# AD_1.net
KiCad netlist of a schematic drawn in Altium Designer
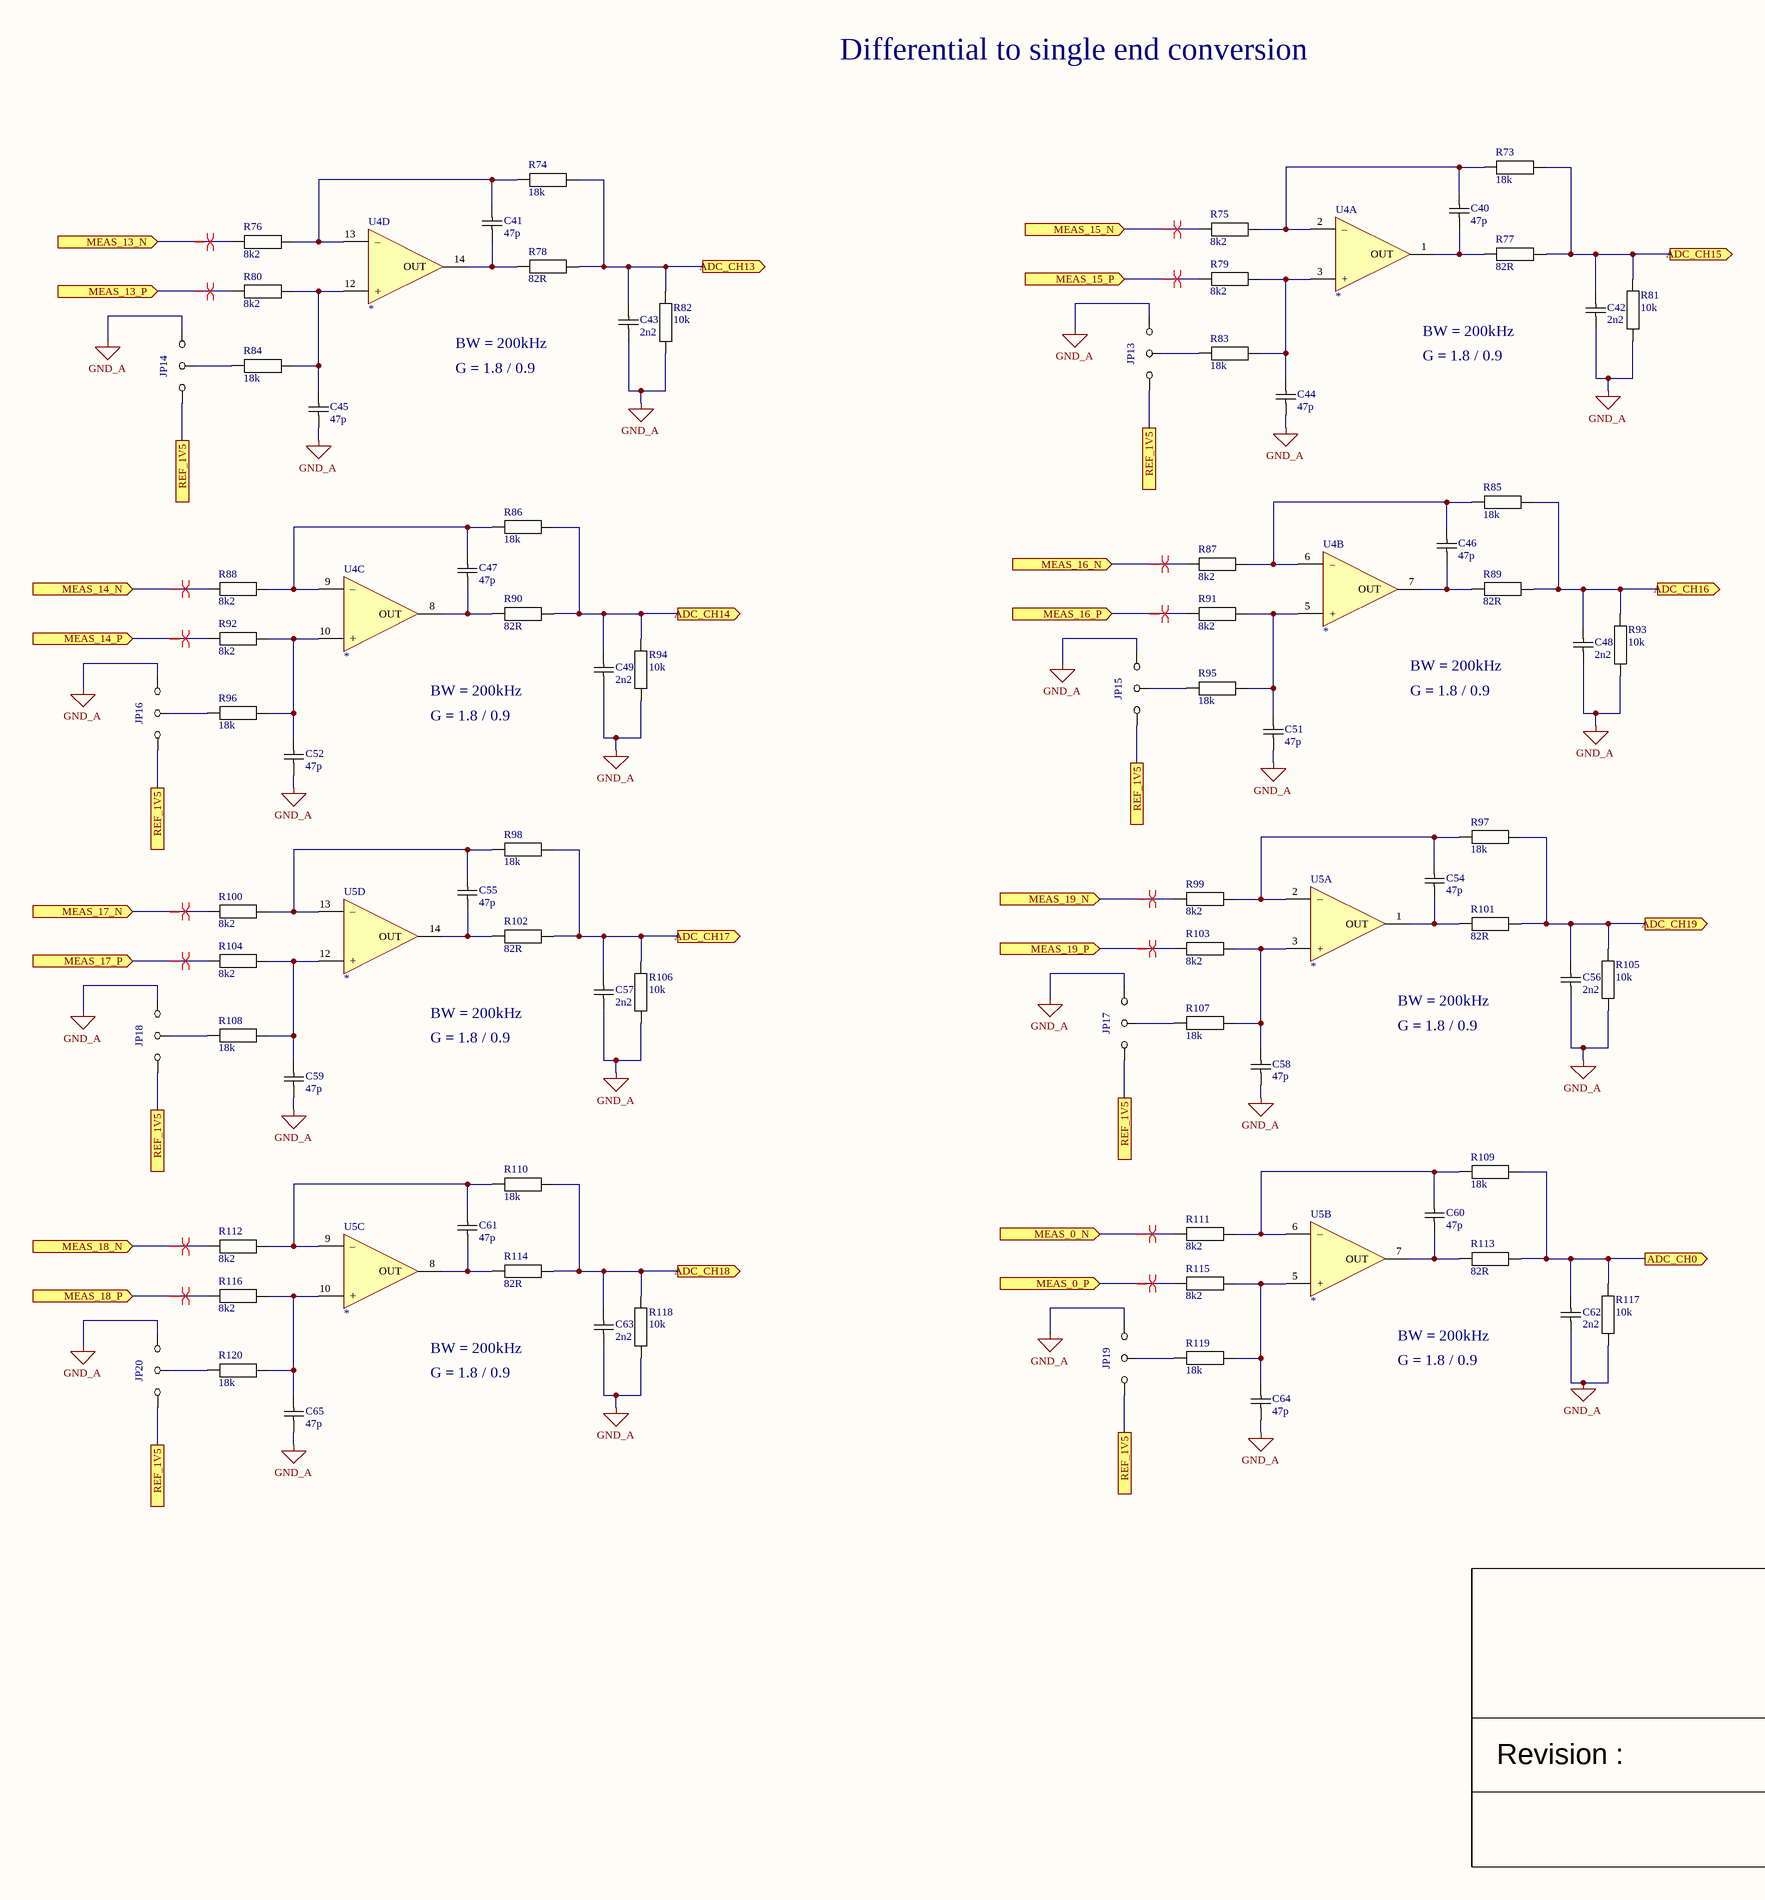
[diagram p0: AD_1.SchDoc, left]
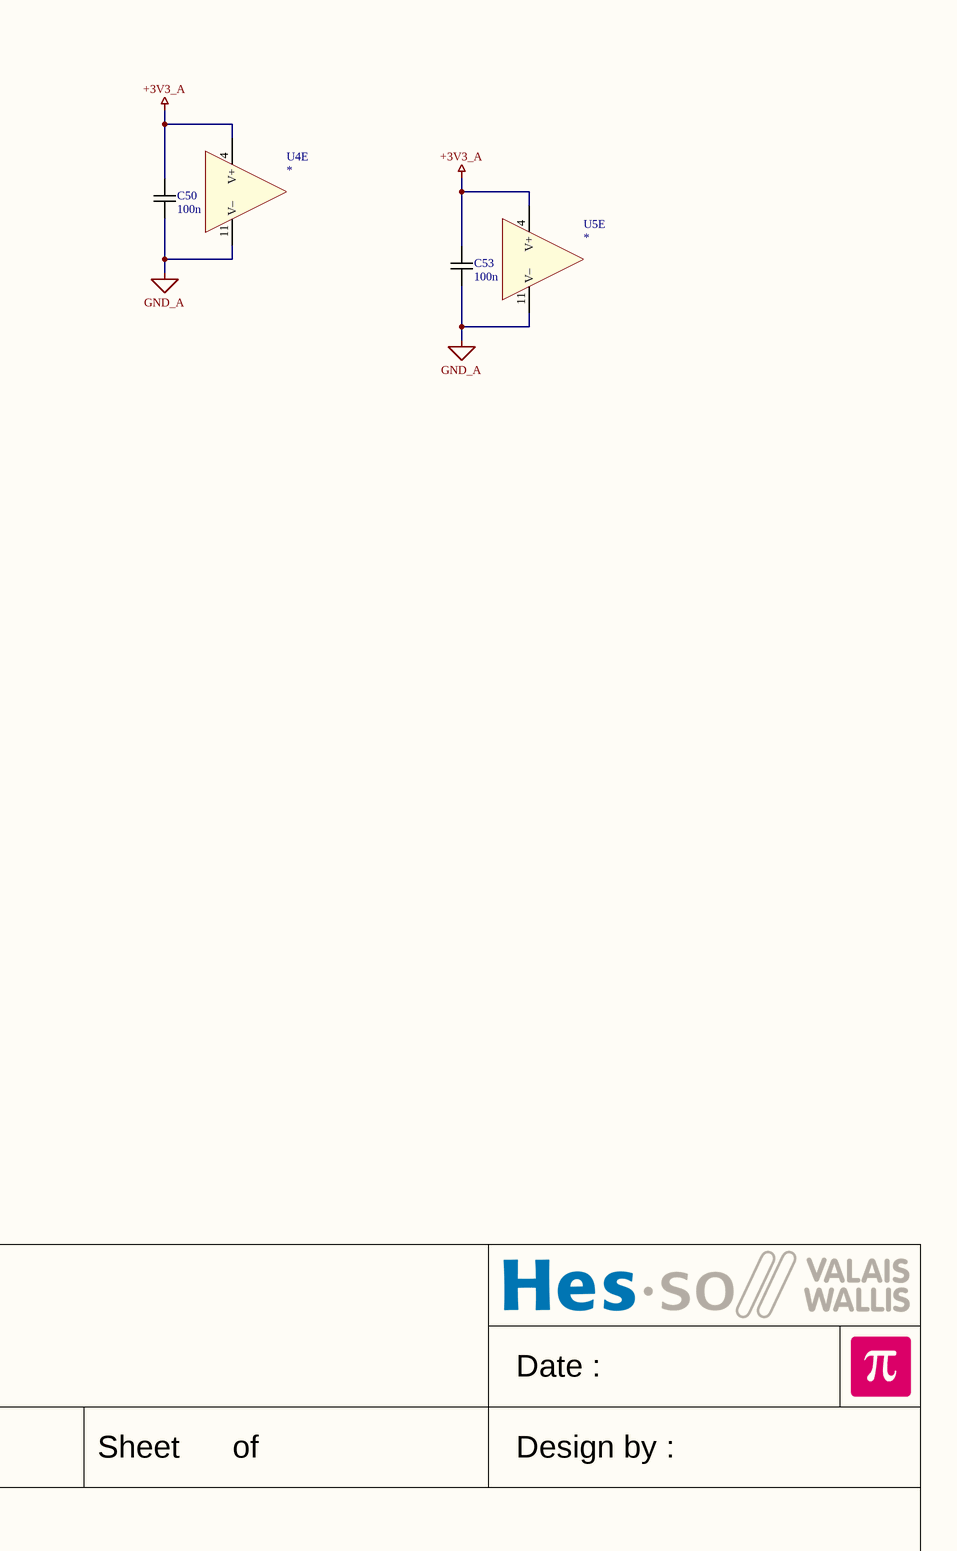
[diagram p1: AD_1.SchDoc, right]

(export (version "E")
  (design (tool "Eeschema 10.0.6"))
  (components
    (comp (ref "C40")
      (value "47p")
      (footprint "CAPACITOR 1608 REFLOW")
      (description "Capacitor X7R 10% 50V 1608(0603)")
      (libsource (lib "Capacitor") (part "Capacitor"))
    )
    (comp (ref "C41")
      (value "47p")
      (footprint "CAPACITOR 1608 REFLOW")
      (description "Capacitor X7R 10% 50V 1608(0603)")
      (libsource (lib "Capacitor") (part "Capacitor"))
    )
    (comp (ref "C42")
      (value "2n2")
      (footprint "CAPACITOR 1608 REFLOW")
      (description "Capacitor X7R 10% 50V 1608(0603)")
      (libsource (lib "Capacitor") (part "Capacitor"))
    )
    (comp (ref "C43")
      (value "2n2")
      (footprint "CAPACITOR 1608 REFLOW")
      (description "Capacitor X7R 10% 50V 1608(0603)")
      (libsource (lib "Capacitor") (part "Capacitor"))
    )
    (comp (ref "C44")
      (value "47p")
      (footprint "CAPACITOR 1608 REFLOW")
      (description "Capacitor X7R 10% 50V 1608(0603)")
      (libsource (lib "Capacitor") (part "Capacitor"))
    )
    (comp (ref "C45")
      (value "47p")
      (footprint "CAPACITOR 1608 REFLOW")
      (description "Capacitor X7R 10% 50V 1608(0603)")
      (libsource (lib "Capacitor") (part "Capacitor"))
    )
    (comp (ref "C46")
      (value "47p")
      (footprint "CAPACITOR 1608 REFLOW")
      (description "Capacitor X7R 10% 50V 1608(0603)")
      (libsource (lib "Capacitor") (part "Capacitor"))
    )
    (comp (ref "C47")
      (value "47p")
      (footprint "CAPACITOR 1608 REFLOW")
      (description "Capacitor X7R 10% 50V 1608(0603)")
      (libsource (lib "Capacitor") (part "Capacitor"))
    )
    (comp (ref "C48")
      (value "2n2")
      (footprint "CAPACITOR 1608 REFLOW")
      (description "Capacitor X7R 10% 50V 1608(0603)")
      (libsource (lib "Capacitor") (part "Capacitor"))
    )
    (comp (ref "C49")
      (value "2n2")
      (footprint "CAPACITOR 1608 REFLOW")
      (description "Capacitor X7R 10% 50V 1608(0603)")
      (libsource (lib "Capacitor") (part "Capacitor"))
    )
    (comp (ref "C50")
      (value "100n")
      (footprint "CAPACITOR 1608 REFLOW")
      (description "Capacitor X7R 10% 50V 1608(0603)")
      (libsource (lib "Capacitor") (part "Capacitor"))
    )
    (comp (ref "C51")
      (value "47p")
      (footprint "CAPACITOR 1608 REFLOW")
      (description "Capacitor X7R 10% 50V 1608(0603)")
      (libsource (lib "Capacitor") (part "Capacitor"))
    )
    (comp (ref "C52")
      (value "47p")
      (footprint "CAPACITOR 1608 REFLOW")
      (description "Capacitor X7R 10% 50V 1608(0603)")
      (libsource (lib "Capacitor") (part "Capacitor"))
    )
    (comp (ref "C53")
      (value "100n")
      (footprint "CAPACITOR 1608 REFLOW")
      (description "Capacitor X7R 10% 50V 1608(0603)")
      (libsource (lib "Capacitor") (part "Capacitor"))
    )
    (comp (ref "C54")
      (value "47p")
      (footprint "CAPACITOR 1608 REFLOW")
      (description "Capacitor X7R 10% 50V 1608(0603)")
      (libsource (lib "Capacitor") (part "Capacitor"))
    )
    (comp (ref "C55")
      (value "47p")
      (footprint "CAPACITOR 1608 REFLOW")
      (description "Capacitor X7R 10% 50V 1608(0603)")
      (libsource (lib "Capacitor") (part "Capacitor"))
    )
    (comp (ref "C56")
      (value "2n2")
      (footprint "CAPACITOR 1608 REFLOW")
      (description "Capacitor X7R 10% 50V 1608(0603)")
      (libsource (lib "Capacitor") (part "Capacitor"))
    )
    (comp (ref "C57")
      (value "2n2")
      (footprint "CAPACITOR 1608 REFLOW")
      (description "Capacitor X7R 10% 50V 1608(0603)")
      (libsource (lib "Capacitor") (part "Capacitor"))
    )
    (comp (ref "C58")
      (value "47p")
      (footprint "CAPACITOR 1608 REFLOW")
      (description "Capacitor X7R 10% 50V 1608(0603)")
      (libsource (lib "Capacitor") (part "Capacitor"))
    )
    (comp (ref "C59")
      (value "47p")
      (footprint "CAPACITOR 1608 REFLOW")
      (description "Capacitor X7R 10% 50V 1608(0603)")
      (libsource (lib "Capacitor") (part "Capacitor"))
    )
    (comp (ref "C60")
      (value "47p")
      (footprint "CAPACITOR 1608 REFLOW")
      (description "Capacitor X7R 10% 50V 1608(0603)")
      (libsource (lib "Capacitor") (part "Capacitor"))
    )
    (comp (ref "C61")
      (value "47p")
      (footprint "CAPACITOR 1608 REFLOW")
      (description "Capacitor X7R 10% 50V 1608(0603)")
      (libsource (lib "Capacitor") (part "Capacitor"))
    )
    (comp (ref "C62")
      (value "2n2")
      (footprint "CAPACITOR 1608 REFLOW")
      (description "Capacitor X7R 10% 50V 1608(0603)")
      (libsource (lib "Capacitor") (part "Capacitor"))
    )
    (comp (ref "C63")
      (value "2n2")
      (footprint "CAPACITOR 1608 REFLOW")
      (description "Capacitor X7R 10% 50V 1608(0603)")
      (libsource (lib "Capacitor") (part "Capacitor"))
    )
    (comp (ref "C64")
      (value "47p")
      (footprint "CAPACITOR 1608 REFLOW")
      (description "Capacitor X7R 10% 50V 1608(0603)")
      (libsource (lib "Capacitor") (part "Capacitor"))
    )
    (comp (ref "C65")
      (value "47p")
      (footprint "CAPACITOR 1608 REFLOW")
      (description "Capacitor X7R 10% 50V 1608(0603)")
      (libsource (lib "Capacitor") (part "Capacitor"))
    )
    (comp (ref "JP13")
      (value "{Value}")
      (footprint "JUMPER3 SMD 1608")
      (description "JUMPER 3 POS")
      (libsource (lib "Jumper") (part "JUMPER 3 POS"))
    )
    (comp (ref "JP14")
      (value "{Value}")
      (footprint "JUMPER3 SMD 1608")
      (description "JUMPER 3 POS")
      (libsource (lib "Jumper") (part "JUMPER 3 POS"))
    )
    (comp (ref "JP15")
      (value "{Value}")
      (footprint "JUMPER3 SMD 1608")
      (description "JUMPER 3 POS")
      (libsource (lib "Jumper") (part "JUMPER 3 POS"))
    )
    (comp (ref "JP16")
      (value "{Value}")
      (footprint "JUMPER3 SMD 1608")
      (description "JUMPER 3 POS")
      (libsource (lib "Jumper") (part "JUMPER 3 POS"))
    )
    (comp (ref "JP17")
      (value "{Value}")
      (footprint "JUMPER3 SMD 1608")
      (description "JUMPER 3 POS")
      (libsource (lib "Jumper") (part "JUMPER 3 POS"))
    )
    (comp (ref "JP18")
      (value "{Value}")
      (footprint "JUMPER3 SMD 1608")
      (description "JUMPER 3 POS")
      (libsource (lib "Jumper") (part "JUMPER 3 POS"))
    )
    (comp (ref "JP19")
      (value "{Value}")
      (footprint "JUMPER3 SMD 1608")
      (description "JUMPER 3 POS")
      (libsource (lib "Jumper") (part "JUMPER 3 POS"))
    )
    (comp (ref "JP20")
      (value "{Value}")
      (footprint "JUMPER3 SMD 1608")
      (description "JUMPER 3 POS")
      (libsource (lib "Jumper") (part "JUMPER 3 POS"))
    )
    (comp (ref "R73")
      (value "18k")
      (footprint "RESISTOR 1608 REFLOW")
      (description "Resistor 1% 50V 100mW 1608(0603)")
      (libsource (lib "Resistor") (part "Resistor"))
    )
    (comp (ref "R74")
      (value "18k")
      (footprint "RESISTOR 1608 REFLOW")
      (description "Resistor 1% 50V 100mW 1608(0603)")
      (libsource (lib "Resistor") (part "Resistor"))
    )
    (comp (ref "R75")
      (value "8k2")
      (footprint "RESISTOR 1608 REFLOW")
      (description "Resistor 1% 50V 100mW 1608(0603)")
      (libsource (lib "Resistor") (part "Resistor"))
    )
    (comp (ref "R76")
      (value "8k2")
      (footprint "RESISTOR 1608 REFLOW")
      (description "Resistor 1% 50V 100mW 1608(0603)")
      (libsource (lib "Resistor") (part "Resistor"))
    )
    (comp (ref "R77")
      (value "82R")
      (footprint "RESISTOR 1608 REFLOW")
      (description "Resistor 1% 50V 100mW 1608(0603)")
      (libsource (lib "Resistor") (part "Resistor"))
    )
    (comp (ref "R78")
      (value "82R")
      (footprint "RESISTOR 1608 REFLOW")
      (description "Resistor 1% 50V 100mW 1608(0603)")
      (libsource (lib "Resistor") (part "Resistor"))
    )
    (comp (ref "R79")
      (value "8k2")
      (footprint "RESISTOR 1608 REFLOW")
      (description "Resistor 1% 50V 100mW 1608(0603)")
      (libsource (lib "Resistor") (part "Resistor"))
    )
    (comp (ref "R80")
      (value "8k2")
      (footprint "RESISTOR 1608 REFLOW")
      (description "Resistor 1% 50V 100mW 1608(0603)")
      (libsource (lib "Resistor") (part "Resistor"))
    )
    (comp (ref "R81")
      (value "10k")
      (footprint "RESISTOR 1608 REFLOW")
      (description "Resistor 1% 50V 100mW 1608(0603)")
      (libsource (lib "Resistor") (part "Resistor"))
    )
    (comp (ref "R82")
      (value "10k")
      (footprint "RESISTOR 1608 REFLOW")
      (description "Resistor 1% 50V 100mW 1608(0603)")
      (libsource (lib "Resistor") (part "Resistor"))
    )
    (comp (ref "R83")
      (value "18k")
      (footprint "RESISTOR 1608 REFLOW")
      (description "Resistor 1% 50V 100mW 1608(0603)")
      (libsource (lib "Resistor") (part "Resistor"))
    )
    (comp (ref "R84")
      (value "18k")
      (footprint "RESISTOR 1608 REFLOW")
      (description "Resistor 1% 50V 100mW 1608(0603)")
      (libsource (lib "Resistor") (part "Resistor"))
    )
    (comp (ref "R85")
      (value "18k")
      (footprint "RESISTOR 1608 REFLOW")
      (description "Resistor 1% 50V 100mW 1608(0603)")
      (libsource (lib "Resistor") (part "Resistor"))
    )
    (comp (ref "R86")
      (value "18k")
      (footprint "RESISTOR 1608 REFLOW")
      (description "Resistor 1% 50V 100mW 1608(0603)")
      (libsource (lib "Resistor") (part "Resistor"))
    )
    (comp (ref "R87")
      (value "8k2")
      (footprint "RESISTOR 1608 REFLOW")
      (description "Resistor 1% 50V 100mW 1608(0603)")
      (libsource (lib "Resistor") (part "Resistor"))
    )
    (comp (ref "R88")
      (value "8k2")
      (footprint "RESISTOR 1608 REFLOW")
      (description "Resistor 1% 50V 100mW 1608(0603)")
      (libsource (lib "Resistor") (part "Resistor"))
    )
    (comp (ref "R89")
      (value "82R")
      (footprint "RESISTOR 1608 REFLOW")
      (description "Resistor 1% 50V 100mW 1608(0603)")
      (libsource (lib "Resistor") (part "Resistor"))
    )
    (comp (ref "R90")
      (value "82R")
      (footprint "RESISTOR 1608 REFLOW")
      (description "Resistor 1% 50V 100mW 1608(0603)")
      (libsource (lib "Resistor") (part "Resistor"))
    )
    (comp (ref "R91")
      (value "8k2")
      (footprint "RESISTOR 1608 REFLOW")
      (description "Resistor 1% 50V 100mW 1608(0603)")
      (libsource (lib "Resistor") (part "Resistor"))
    )
    (comp (ref "R92")
      (value "8k2")
      (footprint "RESISTOR 1608 REFLOW")
      (description "Resistor 1% 50V 100mW 1608(0603)")
      (libsource (lib "Resistor") (part "Resistor"))
    )
    (comp (ref "R93")
      (value "10k")
      (footprint "RESISTOR 1608 REFLOW")
      (description "Resistor 1% 50V 100mW 1608(0603)")
      (libsource (lib "Resistor") (part "Resistor"))
    )
    (comp (ref "R94")
      (value "10k")
      (footprint "RESISTOR 1608 REFLOW")
      (description "Resistor 1% 50V 100mW 1608(0603)")
      (libsource (lib "Resistor") (part "Resistor"))
    )
    (comp (ref "R95")
      (value "18k")
      (footprint "RESISTOR 1608 REFLOW")
      (description "Resistor 1% 50V 100mW 1608(0603)")
      (libsource (lib "Resistor") (part "Resistor"))
    )
    (comp (ref "R96")
      (value "18k")
      (footprint "RESISTOR 1608 REFLOW")
      (description "Resistor 1% 50V 100mW 1608(0603)")
      (libsource (lib "Resistor") (part "Resistor"))
    )
    (comp (ref "R97")
      (value "18k")
      (footprint "RESISTOR 1608 REFLOW")
      (description "Resistor 1% 50V 100mW 1608(0603)")
      (libsource (lib "Resistor") (part "Resistor"))
    )
    (comp (ref "R98")
      (value "18k")
      (footprint "RESISTOR 1608 REFLOW")
      (description "Resistor 1% 50V 100mW 1608(0603)")
      (libsource (lib "Resistor") (part "Resistor"))
    )
    (comp (ref "R99")
      (value "8k2")
      (footprint "RESISTOR 1608 REFLOW")
      (description "Resistor 1% 50V 100mW 1608(0603)")
      (libsource (lib "Resistor") (part "Resistor"))
    )
    (comp (ref "R100")
      (value "8k2")
      (footprint "RESISTOR 1608 REFLOW")
      (description "Resistor 1% 50V 100mW 1608(0603)")
      (libsource (lib "Resistor") (part "Resistor"))
    )
    (comp (ref "R101")
      (value "82R")
      (footprint "RESISTOR 1608 REFLOW")
      (description "Resistor 1% 50V 100mW 1608(0603)")
      (libsource (lib "Resistor") (part "Resistor"))
    )
    (comp (ref "R102")
      (value "82R")
      (footprint "RESISTOR 1608 REFLOW")
      (description "Resistor 1% 50V 100mW 1608(0603)")
      (libsource (lib "Resistor") (part "Resistor"))
    )
    (comp (ref "R103")
      (value "8k2")
      (footprint "RESISTOR 1608 REFLOW")
      (description "Resistor 1% 50V 100mW 1608(0603)")
      (libsource (lib "Resistor") (part "Resistor"))
    )
    (comp (ref "R104")
      (value "8k2")
      (footprint "RESISTOR 1608 REFLOW")
      (description "Resistor 1% 50V 100mW 1608(0603)")
      (libsource (lib "Resistor") (part "Resistor"))
    )
    (comp (ref "R105")
      (value "10k")
      (footprint "RESISTOR 1608 REFLOW")
      (description "Resistor 1% 50V 100mW 1608(0603)")
      (libsource (lib "Resistor") (part "Resistor"))
    )
    (comp (ref "R106")
      (value "10k")
      (footprint "RESISTOR 1608 REFLOW")
      (description "Resistor 1% 50V 100mW 1608(0603)")
      (libsource (lib "Resistor") (part "Resistor"))
    )
    (comp (ref "R107")
      (value "18k")
      (footprint "RESISTOR 1608 REFLOW")
      (description "Resistor 1% 50V 100mW 1608(0603)")
      (libsource (lib "Resistor") (part "Resistor"))
    )
    (comp (ref "R108")
      (value "18k")
      (footprint "RESISTOR 1608 REFLOW")
      (description "Resistor 1% 50V 100mW 1608(0603)")
      (libsource (lib "Resistor") (part "Resistor"))
    )
    (comp (ref "R109")
      (value "18k")
      (footprint "RESISTOR 1608 REFLOW")
      (description "Resistor 1% 50V 100mW 1608(0603)")
      (libsource (lib "Resistor") (part "Resistor"))
    )
    (comp (ref "R110")
      (value "18k")
      (footprint "RESISTOR 1608 REFLOW")
      (description "Resistor 1% 50V 100mW 1608(0603)")
      (libsource (lib "Resistor") (part "Resistor"))
    )
    (comp (ref "R111")
      (value "8k2")
      (footprint "RESISTOR 1608 REFLOW")
      (description "Resistor 1% 50V 100mW 1608(0603)")
      (libsource (lib "Resistor") (part "Resistor"))
    )
    (comp (ref "R112")
      (value "8k2")
      (footprint "RESISTOR 1608 REFLOW")
      (description "Resistor 1% 50V 100mW 1608(0603)")
      (libsource (lib "Resistor") (part "Resistor"))
    )
    (comp (ref "R113")
      (value "82R")
      (footprint "RESISTOR 1608 REFLOW")
      (description "Resistor 1% 50V 100mW 1608(0603)")
      (libsource (lib "Resistor") (part "Resistor"))
    )
    (comp (ref "R114")
      (value "82R")
      (footprint "RESISTOR 1608 REFLOW")
      (description "Resistor 1% 50V 100mW 1608(0603)")
      (libsource (lib "Resistor") (part "Resistor"))
    )
    (comp (ref "R115")
      (value "8k2")
      (footprint "RESISTOR 1608 REFLOW")
      (description "Resistor 1% 50V 100mW 1608(0603)")
      (libsource (lib "Resistor") (part "Resistor"))
    )
    (comp (ref "R116")
      (value "8k2")
      (footprint "RESISTOR 1608 REFLOW")
      (description "Resistor 1% 50V 100mW 1608(0603)")
      (libsource (lib "Resistor") (part "Resistor"))
    )
    (comp (ref "R117")
      (value "10k")
      (footprint "RESISTOR 1608 REFLOW")
      (description "Resistor 1% 50V 100mW 1608(0603)")
      (libsource (lib "Resistor") (part "Resistor"))
    )
    (comp (ref "R118")
      (value "10k")
      (footprint "RESISTOR 1608 REFLOW")
      (description "Resistor 1% 50V 100mW 1608(0603)")
      (libsource (lib "Resistor") (part "Resistor"))
    )
    (comp (ref "R119")
      (value "18k")
      (footprint "RESISTOR 1608 REFLOW")
      (description "Resistor 1% 50V 100mW 1608(0603)")
      (libsource (lib "Resistor") (part "Resistor"))
    )
    (comp (ref "R120")
      (value "18k")
      (footprint "RESISTOR 1608 REFLOW")
      (description "Resistor 1% 50V 100mW 1608(0603)")
      (libsource (lib "Resistor") (part "Resistor"))
    )
    (comp (ref "U4")
      (value "*")
      (footprint "SO14 P1.27 C4.0X8.8 H1.75")
      (description "Generic quad OPA 14 pins")
      (libsource (lib "Amplifier") (part "OPA QUAD"))
    )
    (comp (ref "U5")
      (value "*")
      (footprint "SO14 P1.27 C4.0X8.8 H1.75")
      (description "Generic quad OPA 14 pins")
      (libsource (lib "Amplifier") (part "OPA QUAD"))
    )
  )
  (nets
    (net (code "1") (name "+3V3_A") (class "Default")
      (node (ref "C50") (pin "2") (pinfunction "2_2") (pintype "passive"))
      (node (ref "C53") (pin "2") (pinfunction "2_2") (pintype "passive"))
      (node (ref "U4") (pin "4") (pinfunction "V+_4") (pintype "passive"))
      (node (ref "U5") (pin "4") (pinfunction "V+_4") (pintype "passive"))
    )
    (net (code "2") (name "/ADC_CH0") (class "Default")
      (node (ref "C62") (pin "2") (pinfunction "2_2") (pintype "passive"))
      (node (ref "R109") (pin "2") (pinfunction "2_2") (pintype "passive"))
      (node (ref "R113") (pin "2") (pinfunction "2_2") (pintype "passive"))
      (node (ref "R117") (pin "1") (pinfunction "1_1") (pintype "passive"))
    )
    (net (code "3") (name "/ADC_CH13") (class "Default")
      (node (ref "C43") (pin "2") (pinfunction "2_2") (pintype "passive"))
      (node (ref "R74") (pin "2") (pinfunction "2_2") (pintype "passive"))
      (node (ref "R78") (pin "2") (pinfunction "2_2") (pintype "passive"))
      (node (ref "R82") (pin "1") (pinfunction "1_1") (pintype "passive"))
    )
    (net (code "4") (name "/ADC_CH14") (class "Default")
      (node (ref "C49") (pin "2") (pinfunction "2_2") (pintype "passive"))
      (node (ref "R86") (pin "2") (pinfunction "2_2") (pintype "passive"))
      (node (ref "R90") (pin "2") (pinfunction "2_2") (pintype "passive"))
      (node (ref "R94") (pin "1") (pinfunction "1_1") (pintype "passive"))
    )
    (net (code "5") (name "/ADC_CH15") (class "Default")
      (node (ref "C42") (pin "2") (pinfunction "2_2") (pintype "passive"))
      (node (ref "R73") (pin "2") (pinfunction "2_2") (pintype "passive"))
      (node (ref "R77") (pin "2") (pinfunction "2_2") (pintype "passive"))
      (node (ref "R81") (pin "1") (pinfunction "1_1") (pintype "passive"))
    )
    (net (code "6") (name "/ADC_CH16") (class "Default")
      (node (ref "C48") (pin "2") (pinfunction "2_2") (pintype "passive"))
      (node (ref "R85") (pin "2") (pinfunction "2_2") (pintype "passive"))
      (node (ref "R89") (pin "2") (pinfunction "2_2") (pintype "passive"))
      (node (ref "R93") (pin "1") (pinfunction "1_1") (pintype "passive"))
    )
    (net (code "7") (name "/ADC_CH17") (class "Default")
      (node (ref "C57") (pin "2") (pinfunction "2_2") (pintype "passive"))
      (node (ref "R102") (pin "2") (pinfunction "2_2") (pintype "passive"))
      (node (ref "R106") (pin "1") (pinfunction "1_1") (pintype "passive"))
      (node (ref "R98") (pin "2") (pinfunction "2_2") (pintype "passive"))
    )
    (net (code "8") (name "/ADC_CH18") (class "Default")
      (node (ref "C63") (pin "2") (pinfunction "2_2") (pintype "passive"))
      (node (ref "R110") (pin "2") (pinfunction "2_2") (pintype "passive"))
      (node (ref "R114") (pin "2") (pinfunction "2_2") (pintype "passive"))
      (node (ref "R118") (pin "1") (pinfunction "1_1") (pintype "passive"))
    )
    (net (code "9") (name "/ADC_CH19") (class "Default")
      (node (ref "C56") (pin "2") (pinfunction "2_2") (pintype "passive"))
      (node (ref "R101") (pin "2") (pinfunction "2_2") (pintype "passive"))
      (node (ref "R105") (pin "1") (pinfunction "1_1") (pintype "passive"))
      (node (ref "R97") (pin "2") (pinfunction "2_2") (pintype "passive"))
    )
    (net (code "10") (name "/MEAS_0_N") (class "Default")
      (node (ref "R111") (pin "1") (pinfunction "1_1") (pintype "passive"))
    )
    (net (code "11") (name "/MEAS_0_P") (class "Default")
      (node (ref "R115") (pin "1") (pinfunction "1_1") (pintype "passive"))
    )
    (net (code "12") (name "/MEAS_13_N") (class "Default")
      (node (ref "R76") (pin "1") (pinfunction "1_1") (pintype "passive"))
    )
    (net (code "13") (name "/MEAS_13_P") (class "Default")
      (node (ref "R80") (pin "1") (pinfunction "1_1") (pintype "passive"))
    )
    (net (code "14") (name "/MEAS_14_N") (class "Default")
      (node (ref "R88") (pin "1") (pinfunction "1_1") (pintype "passive"))
    )
    (net (code "15") (name "/MEAS_14_P") (class "Default")
      (node (ref "R92") (pin "1") (pinfunction "1_1") (pintype "passive"))
    )
    (net (code "16") (name "/MEAS_15_N") (class "Default")
      (node (ref "R75") (pin "1") (pinfunction "1_1") (pintype "passive"))
    )
    (net (code "17") (name "/MEAS_15_P") (class "Default")
      (node (ref "R79") (pin "1") (pinfunction "1_1") (pintype "passive"))
    )
    (net (code "18") (name "/MEAS_16_N") (class "Default")
      (node (ref "R87") (pin "1") (pinfunction "1_1") (pintype "passive"))
    )
    (net (code "19") (name "/MEAS_16_P") (class "Default")
      (node (ref "R91") (pin "1") (pinfunction "1_1") (pintype "passive"))
    )
    (net (code "20") (name "/MEAS_17_N") (class "Default")
      (node (ref "R100") (pin "1") (pinfunction "1_1") (pintype "passive"))
    )
    (net (code "21") (name "/MEAS_17_P") (class "Default")
      (node (ref "R104") (pin "1") (pinfunction "1_1") (pintype "passive"))
    )
    (net (code "22") (name "/MEAS_18_N") (class "Default")
      (node (ref "R112") (pin "1") (pinfunction "1_1") (pintype "passive"))
    )
    (net (code "23") (name "/MEAS_18_P") (class "Default")
      (node (ref "R116") (pin "1") (pinfunction "1_1") (pintype "passive"))
    )
    (net (code "24") (name "/MEAS_19_N") (class "Default")
      (node (ref "R99") (pin "1") (pinfunction "1_1") (pintype "passive"))
    )
    (net (code "25") (name "/MEAS_19_P") (class "Default")
      (node (ref "R103") (pin "1") (pinfunction "1_1") (pintype "passive"))
    )
    (net (code "26") (name "/REF_1V5") (class "Default")
      (node (ref "JP13") (pin "1") (pinfunction "1_1") (pintype "passive"))
      (node (ref "JP14") (pin "1") (pinfunction "1_1") (pintype "passive"))
      (node (ref "JP15") (pin "1") (pinfunction "1_1") (pintype "passive"))
      (node (ref "JP16") (pin "1") (pinfunction "1_1") (pintype "passive"))
      (node (ref "JP17") (pin "1") (pinfunction "1_1") (pintype "passive"))
      (node (ref "JP18") (pin "1") (pinfunction "1_1") (pintype "passive"))
      (node (ref "JP19") (pin "1") (pinfunction "1_1") (pintype "passive"))
      (node (ref "JP20") (pin "1") (pinfunction "1_1") (pintype "passive"))
    )
    (net (code "27") (name "GND_A") (class "Default")
      (node (ref "C42") (pin "1") (pinfunction "1_1") (pintype "passive"))
      (node (ref "C43") (pin "1") (pinfunction "1_1") (pintype "passive"))
      (node (ref "C44") (pin "1") (pinfunction "1_1") (pintype "passive"))
      (node (ref "C45") (pin "1") (pinfunction "1_1") (pintype "passive"))
      (node (ref "C48") (pin "1") (pinfunction "1_1") (pintype "passive"))
      (node (ref "C49") (pin "1") (pinfunction "1_1") (pintype "passive"))
      (node (ref "C50") (pin "1") (pinfunction "1_1") (pintype "passive"))
      (node (ref "C51") (pin "1") (pinfunction "1_1") (pintype "passive"))
      (node (ref "C52") (pin "1") (pinfunction "1_1") (pintype "passive"))
      (node (ref "C53") (pin "1") (pinfunction "1_1") (pintype "passive"))
      (node (ref "C56") (pin "1") (pinfunction "1_1") (pintype "passive"))
      (node (ref "C57") (pin "1") (pinfunction "1_1") (pintype "passive"))
      (node (ref "C58") (pin "1") (pinfunction "1_1") (pintype "passive"))
      (node (ref "C59") (pin "1") (pinfunction "1_1") (pintype "passive"))
      (node (ref "C62") (pin "1") (pinfunction "1_1") (pintype "passive"))
      (node (ref "C63") (pin "1") (pinfunction "1_1") (pintype "passive"))
      (node (ref "C64") (pin "1") (pinfunction "1_1") (pintype "passive"))
      (node (ref "C65") (pin "1") (pinfunction "1_1") (pintype "passive"))
      (node (ref "JP13") (pin "3") (pinfunction "3_3") (pintype "passive"))
      (node (ref "JP14") (pin "3") (pinfunction "3_3") (pintype "passive"))
      (node (ref "JP15") (pin "3") (pinfunction "3_3") (pintype "passive"))
      (node (ref "JP16") (pin "3") (pinfunction "3_3") (pintype "passive"))
      (node (ref "JP17") (pin "3") (pinfunction "3_3") (pintype "passive"))
      (node (ref "JP18") (pin "3") (pinfunction "3_3") (pintype "passive"))
      (node (ref "JP19") (pin "3") (pinfunction "3_3") (pintype "passive"))
      (node (ref "JP20") (pin "3") (pinfunction "3_3") (pintype "passive"))
      (node (ref "R105") (pin "2") (pinfunction "2_2") (pintype "passive"))
      (node (ref "R106") (pin "2") (pinfunction "2_2") (pintype "passive"))
      (node (ref "R117") (pin "2") (pinfunction "2_2") (pintype "passive"))
      (node (ref "R118") (pin "2") (pinfunction "2_2") (pintype "passive"))
      (node (ref "R81") (pin "2") (pinfunction "2_2") (pintype "passive"))
      (node (ref "R82") (pin "2") (pinfunction "2_2") (pintype "passive"))
      (node (ref "R93") (pin "2") (pinfunction "2_2") (pintype "passive"))
      (node (ref "R94") (pin "2") (pinfunction "2_2") (pintype "passive"))
      (node (ref "U4") (pin "11") (pinfunction "V–_11") (pintype "passive"))
      (node (ref "U5") (pin "11") (pinfunction "V–_11") (pintype "passive"))
    )
    (net (code "28") (name "Net-(JP13-Pad2)") (class "Default")
      (node (ref "JP13") (pin "2") (pinfunction "2_2") (pintype "passive"))
      (node (ref "R83") (pin "2") (pinfunction "2_2") (pintype "passive"))
    )
    (net (code "29") (name "Net-(JP14-Pad2)") (class "Default")
      (node (ref "JP14") (pin "2") (pinfunction "2_2") (pintype "passive"))
      (node (ref "R84") (pin "2") (pinfunction "2_2") (pintype "passive"))
    )
    (net (code "30") (name "Net-(JP15-Pad2)") (class "Default")
      (node (ref "JP15") (pin "2") (pinfunction "2_2") (pintype "passive"))
      (node (ref "R95") (pin "2") (pinfunction "2_2") (pintype "passive"))
    )
    (net (code "31") (name "Net-(JP16-Pad2)") (class "Default")
      (node (ref "JP16") (pin "2") (pinfunction "2_2") (pintype "passive"))
      (node (ref "R96") (pin "2") (pinfunction "2_2") (pintype "passive"))
    )
    (net (code "32") (name "Net-(JP17-Pad2)") (class "Default")
      (node (ref "JP17") (pin "2") (pinfunction "2_2") (pintype "passive"))
      (node (ref "R107") (pin "2") (pinfunction "2_2") (pintype "passive"))
    )
    (net (code "33") (name "Net-(JP18-Pad2)") (class "Default")
      (node (ref "JP18") (pin "2") (pinfunction "2_2") (pintype "passive"))
      (node (ref "R108") (pin "2") (pinfunction "2_2") (pintype "passive"))
    )
    (net (code "34") (name "Net-(JP19-Pad2)") (class "Default")
      (node (ref "JP19") (pin "2") (pinfunction "2_2") (pintype "passive"))
      (node (ref "R119") (pin "2") (pinfunction "2_2") (pintype "passive"))
    )
    (net (code "35") (name "Net-(JP20-Pad2)") (class "Default")
      (node (ref "JP20") (pin "2") (pinfunction "2_2") (pintype "passive"))
      (node (ref "R120") (pin "2") (pinfunction "2_2") (pintype "passive"))
    )
    (net (code "36") (name "Net-(U4A-+)") (class "Default")
      (node (ref "C44") (pin "2") (pinfunction "2_2") (pintype "passive"))
      (node (ref "R79") (pin "2") (pinfunction "2_2") (pintype "passive"))
      (node (ref "R83") (pin "1") (pinfunction "1_1") (pintype "passive"))
      (node (ref "U4") (pin "3") (pinfunction "+_3") (pintype "passive"))
    )
    (net (code "37") (name "Net-(U4A-OUT)") (class "Default")
      (node (ref "C40") (pin "1") (pinfunction "1_1") (pintype "passive"))
      (node (ref "R77") (pin "1") (pinfunction "1_1") (pintype "passive"))
      (node (ref "U4") (pin "1") (pinfunction "OUT_1") (pintype "passive"))
    )
    (net (code "38") (name "Net-(U4A-–)") (class "Default")
      (node (ref "C40") (pin "2") (pinfunction "2_2") (pintype "passive"))
      (node (ref "R73") (pin "1") (pinfunction "1_1") (pintype "passive"))
      (node (ref "R75") (pin "2") (pinfunction "2_2") (pintype "passive"))
      (node (ref "U4") (pin "2") (pinfunction "–_2") (pintype "passive"))
    )
    (net (code "39") (name "Net-(U4B-+)") (class "Default")
      (node (ref "C51") (pin "2") (pinfunction "2_2") (pintype "passive"))
      (node (ref "R91") (pin "2") (pinfunction "2_2") (pintype "passive"))
      (node (ref "R95") (pin "1") (pinfunction "1_1") (pintype "passive"))
      (node (ref "U4") (pin "5") (pinfunction "+_5") (pintype "passive"))
    )
    (net (code "40") (name "Net-(U4B-OUT)") (class "Default")
      (node (ref "C46") (pin "1") (pinfunction "1_1") (pintype "passive"))
      (node (ref "R89") (pin "1") (pinfunction "1_1") (pintype "passive"))
      (node (ref "U4") (pin "7") (pinfunction "OUT_7") (pintype "passive"))
    )
    (net (code "41") (name "Net-(U4B-–)") (class "Default")
      (node (ref "C46") (pin "2") (pinfunction "2_2") (pintype "passive"))
      (node (ref "R85") (pin "1") (pinfunction "1_1") (pintype "passive"))
      (node (ref "R87") (pin "2") (pinfunction "2_2") (pintype "passive"))
      (node (ref "U4") (pin "6") (pinfunction "–_6") (pintype "passive"))
    )
    (net (code "42") (name "Net-(U4C-+)") (class "Default")
      (node (ref "C52") (pin "2") (pinfunction "2_2") (pintype "passive"))
      (node (ref "R92") (pin "2") (pinfunction "2_2") (pintype "passive"))
      (node (ref "R96") (pin "1") (pinfunction "1_1") (pintype "passive"))
      (node (ref "U4") (pin "10") (pinfunction "+_10") (pintype "passive"))
    )
    (net (code "43") (name "Net-(U4C-OUT)") (class "Default")
      (node (ref "C47") (pin "1") (pinfunction "1_1") (pintype "passive"))
      (node (ref "R90") (pin "1") (pinfunction "1_1") (pintype "passive"))
      (node (ref "U4") (pin "8") (pinfunction "OUT_8") (pintype "passive"))
    )
    (net (code "44") (name "Net-(U4C-–)") (class "Default")
      (node (ref "C47") (pin "2") (pinfunction "2_2") (pintype "passive"))
      (node (ref "R86") (pin "1") (pinfunction "1_1") (pintype "passive"))
      (node (ref "R88") (pin "2") (pinfunction "2_2") (pintype "passive"))
      (node (ref "U4") (pin "9") (pinfunction "–_9") (pintype "passive"))
    )
    (net (code "45") (name "Net-(U4D-+)") (class "Default")
      (node (ref "C45") (pin "2") (pinfunction "2_2") (pintype "passive"))
      (node (ref "R80") (pin "2") (pinfunction "2_2") (pintype "passive"))
      (node (ref "R84") (pin "1") (pinfunction "1_1") (pintype "passive"))
      (node (ref "U4") (pin "12") (pinfunction "+_12") (pintype "passive"))
    )
    (net (code "46") (name "Net-(U4D-OUT)") (class "Default")
      (node (ref "C41") (pin "1") (pinfunction "1_1") (pintype "passive"))
      (node (ref "R78") (pin "1") (pinfunction "1_1") (pintype "passive"))
      (node (ref "U4") (pin "14") (pinfunction "OUT_14") (pintype "passive"))
    )
    (net (code "47") (name "Net-(U4D-–)") (class "Default")
      (node (ref "C41") (pin "2") (pinfunction "2_2") (pintype "passive"))
      (node (ref "R74") (pin "1") (pinfunction "1_1") (pintype "passive"))
      (node (ref "R76") (pin "2") (pinfunction "2_2") (pintype "passive"))
      (node (ref "U4") (pin "13") (pinfunction "–_13") (pintype "passive"))
    )
    (net (code "48") (name "Net-(U5A-+)") (class "Default")
      (node (ref "C58") (pin "2") (pinfunction "2_2") (pintype "passive"))
      (node (ref "R103") (pin "2") (pinfunction "2_2") (pintype "passive"))
      (node (ref "R107") (pin "1") (pinfunction "1_1") (pintype "passive"))
      (node (ref "U5") (pin "3") (pinfunction "+_3") (pintype "passive"))
    )
    (net (code "49") (name "Net-(U5A-OUT)") (class "Default")
      (node (ref "C54") (pin "1") (pinfunction "1_1") (pintype "passive"))
      (node (ref "R101") (pin "1") (pinfunction "1_1") (pintype "passive"))
      (node (ref "U5") (pin "1") (pinfunction "OUT_1") (pintype "passive"))
    )
    (net (code "50") (name "Net-(U5A-–)") (class "Default")
      (node (ref "C54") (pin "2") (pinfunction "2_2") (pintype "passive"))
      (node (ref "R97") (pin "1") (pinfunction "1_1") (pintype "passive"))
      (node (ref "R99") (pin "2") (pinfunction "2_2") (pintype "passive"))
      (node (ref "U5") (pin "2") (pinfunction "–_2") (pintype "passive"))
    )
    (net (code "51") (name "Net-(U5B-+)") (class "Default")
      (node (ref "C64") (pin "2") (pinfunction "2_2") (pintype "passive"))
      (node (ref "R115") (pin "2") (pinfunction "2_2") (pintype "passive"))
      (node (ref "R119") (pin "1") (pinfunction "1_1") (pintype "passive"))
      (node (ref "U5") (pin "5") (pinfunction "+_5") (pintype "passive"))
    )
    (net (code "52") (name "Net-(U5B-OUT)") (class "Default")
      (node (ref "C60") (pin "1") (pinfunction "1_1") (pintype "passive"))
      (node (ref "R113") (pin "1") (pinfunction "1_1") (pintype "passive"))
      (node (ref "U5") (pin "7") (pinfunction "OUT_7") (pintype "passive"))
    )
    (net (code "53") (name "Net-(U5B-–)") (class "Default")
      (node (ref "C60") (pin "2") (pinfunction "2_2") (pintype "passive"))
      (node (ref "R109") (pin "1") (pinfunction "1_1") (pintype "passive"))
      (node (ref "R111") (pin "2") (pinfunction "2_2") (pintype "passive"))
      (node (ref "U5") (pin "6") (pinfunction "–_6") (pintype "passive"))
    )
    (net (code "54") (name "Net-(U5C-+)") (class "Default")
      (node (ref "C65") (pin "2") (pinfunction "2_2") (pintype "passive"))
      (node (ref "R116") (pin "2") (pinfunction "2_2") (pintype "passive"))
      (node (ref "R120") (pin "1") (pinfunction "1_1") (pintype "passive"))
      (node (ref "U5") (pin "10") (pinfunction "+_10") (pintype "passive"))
    )
    (net (code "55") (name "Net-(U5C-OUT)") (class "Default")
      (node (ref "C61") (pin "1") (pinfunction "1_1") (pintype "passive"))
      (node (ref "R114") (pin "1") (pinfunction "1_1") (pintype "passive"))
      (node (ref "U5") (pin "8") (pinfunction "OUT_8") (pintype "passive"))
    )
    (net (code "56") (name "Net-(U5C-–)") (class "Default")
      (node (ref "C61") (pin "2") (pinfunction "2_2") (pintype "passive"))
      (node (ref "R110") (pin "1") (pinfunction "1_1") (pintype "passive"))
      (node (ref "R112") (pin "2") (pinfunction "2_2") (pintype "passive"))
      (node (ref "U5") (pin "9") (pinfunction "–_9") (pintype "passive"))
    )
    (net (code "57") (name "Net-(U5D-+)") (class "Default")
      (node (ref "C59") (pin "2") (pinfunction "2_2") (pintype "passive"))
      (node (ref "R104") (pin "2") (pinfunction "2_2") (pintype "passive"))
      (node (ref "R108") (pin "1") (pinfunction "1_1") (pintype "passive"))
      (node (ref "U5") (pin "12") (pinfunction "+_12") (pintype "passive"))
    )
    (net (code "58") (name "Net-(U5D-OUT)") (class "Default")
      (node (ref "C55") (pin "1") (pinfunction "1_1") (pintype "passive"))
      (node (ref "R102") (pin "1") (pinfunction "1_1") (pintype "passive"))
      (node (ref "U5") (pin "14") (pinfunction "OUT_14") (pintype "passive"))
    )
    (net (code "59") (name "Net-(U5D-–)") (class "Default")
      (node (ref "C55") (pin "2") (pinfunction "2_2") (pintype "passive"))
      (node (ref "R100") (pin "2") (pinfunction "2_2") (pintype "passive"))
      (node (ref "R98") (pin "1") (pinfunction "1_1") (pintype "passive"))
      (node (ref "U5") (pin "13") (pinfunction "–_13") (pintype "passive"))
    )
  )
)
